# SensorBoards.net
KiCad netlist of a schematic drawn in EAGLE
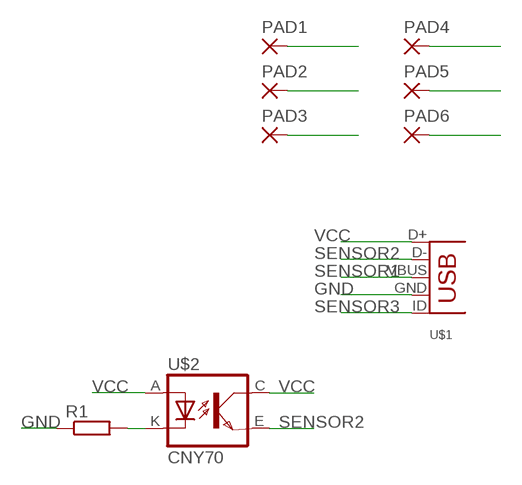
[diagram p0: schematic, sheet 1]

(export (version "E")
  (design (tool "Eeschema 10.0.6"))
  (components
    (comp (ref "PAD1")
      (value "WIREPADSMD2,54-5,08")
      (footprint "eagle-import:SMD2,54-5,08")
      (libsource (lib "eagle-import") (part "WIREPADSMD2,54-5,08"))
    )
    (comp (ref "PAD2")
      (value "WIREPADSMD2,54-5,08")
      (footprint "eagle-import:SMD2,54-5,08")
      (libsource (lib "eagle-import") (part "WIREPADSMD2,54-5,08"))
    )
    (comp (ref "PAD3")
      (value "WIREPADSMD2,54-5,08")
      (footprint "eagle-import:SMD2,54-5,08")
      (libsource (lib "eagle-import") (part "WIREPADSMD2,54-5,08"))
    )
    (comp (ref "PAD4")
      (value "WIREPADSMD2,54-5,08")
      (footprint "eagle-import:SMD2,54-5,08")
      (libsource (lib "eagle-import") (part "WIREPADSMD2,54-5,08"))
    )
    (comp (ref "PAD5")
      (value "WIREPADSMD2,54-5,08")
      (footprint "eagle-import:SMD2,54-5,08")
      (libsource (lib "eagle-import") (part "WIREPADSMD2,54-5,08"))
    )
    (comp (ref "PAD6")
      (value "WIREPADSMD2,54-5,08")
      (footprint "eagle-import:SMD2,54-5,08")
      (libsource (lib "eagle-import") (part "WIREPADSMD2,54-5,08"))
    )
    (comp (ref "R1")
      (value "RCL_R-EU_R0805")
      (footprint "eagle-import:RCL_R0805")
      (libsource (lib "eagle-import") (part "RCL_R-EU_R0805"))
    )
    (comp (ref "U$1")
      (value "MOLES-USB-MICRO")
      (footprint "eagle-import:MOLEX-USB-MICRO")
      (libsource (lib "eagle-import") (part "MOLES-USB-MICRO"))
    )
    (comp (ref "U$2")
      (value "CNY70")
      (footprint "eagle-import:4")
      (libsource (lib "eagle-import") (part "CNY70"))
    )
  )
  (nets
    (net (code "1") (name "/GND") (class "Default")
      (node (ref "PAD3") (pin "1") (pinfunction "P_1") (pintype "passive"))
      (node (ref "PAD6") (pin "1") (pinfunction "P_1") (pintype "passive"))
      (node (ref "R1") (pin "1") (pinfunction "1_1") (pintype "passive"))
      (node (ref "U$1") (pin "GND") (pinfunction "GND_GND") (pintype "bidirectional"))
    )
    (net (code "2") (name "/SENSOR1") (class "Default")
      (node (ref "PAD2") (pin "1") (pinfunction "P_1") (pintype "passive"))
      (node (ref "U$1") (pin "VBUS") (pinfunction "VBUS_VBUS") (pintype "bidirectional"))
    )
    (net (code "3") (name "/SENSOR2") (class "Default")
      (node (ref "U$1") (pin "D-") (pinfunction "D-_D-") (pintype "bidirectional"))
      (node (ref "U$2") (pin "E") (pinfunction "EMI_E") (pintype "passive"))
    )
    (net (code "4") (name "/SENSOR3") (class "Default")
      (node (ref "PAD5") (pin "1") (pinfunction "P_1") (pintype "passive"))
      (node (ref "U$1") (pin "ID") (pinfunction "ID_ID") (pintype "bidirectional"))
    )
    (net (code "5") (name "/VCC") (class "Default")
      (node (ref "PAD1") (pin "1") (pinfunction "P_1") (pintype "passive"))
      (node (ref "PAD4") (pin "1") (pinfunction "P_1") (pintype "passive"))
      (node (ref "U$1") (pin "D+") (pinfunction "D+_D+") (pintype "bidirectional"))
      (node (ref "U$2") (pin "A") (pinfunction "A_A") (pintype "passive"))
      (node (ref "U$2") (pin "C") (pinfunction "COL_C") (pintype "passive"))
    )
    (net (code "6") (name "Net-(U$2-C)") (class "Default")
      (node (ref "R1") (pin "2") (pinfunction "2_2") (pintype "passive"))
      (node (ref "U$2") (pin "K") (pinfunction "C_K") (pintype "passive"))
    )
  )
)
